# pico_tracker_v3_2.net
KiCad netlist of a schematic drawn in EAGLE
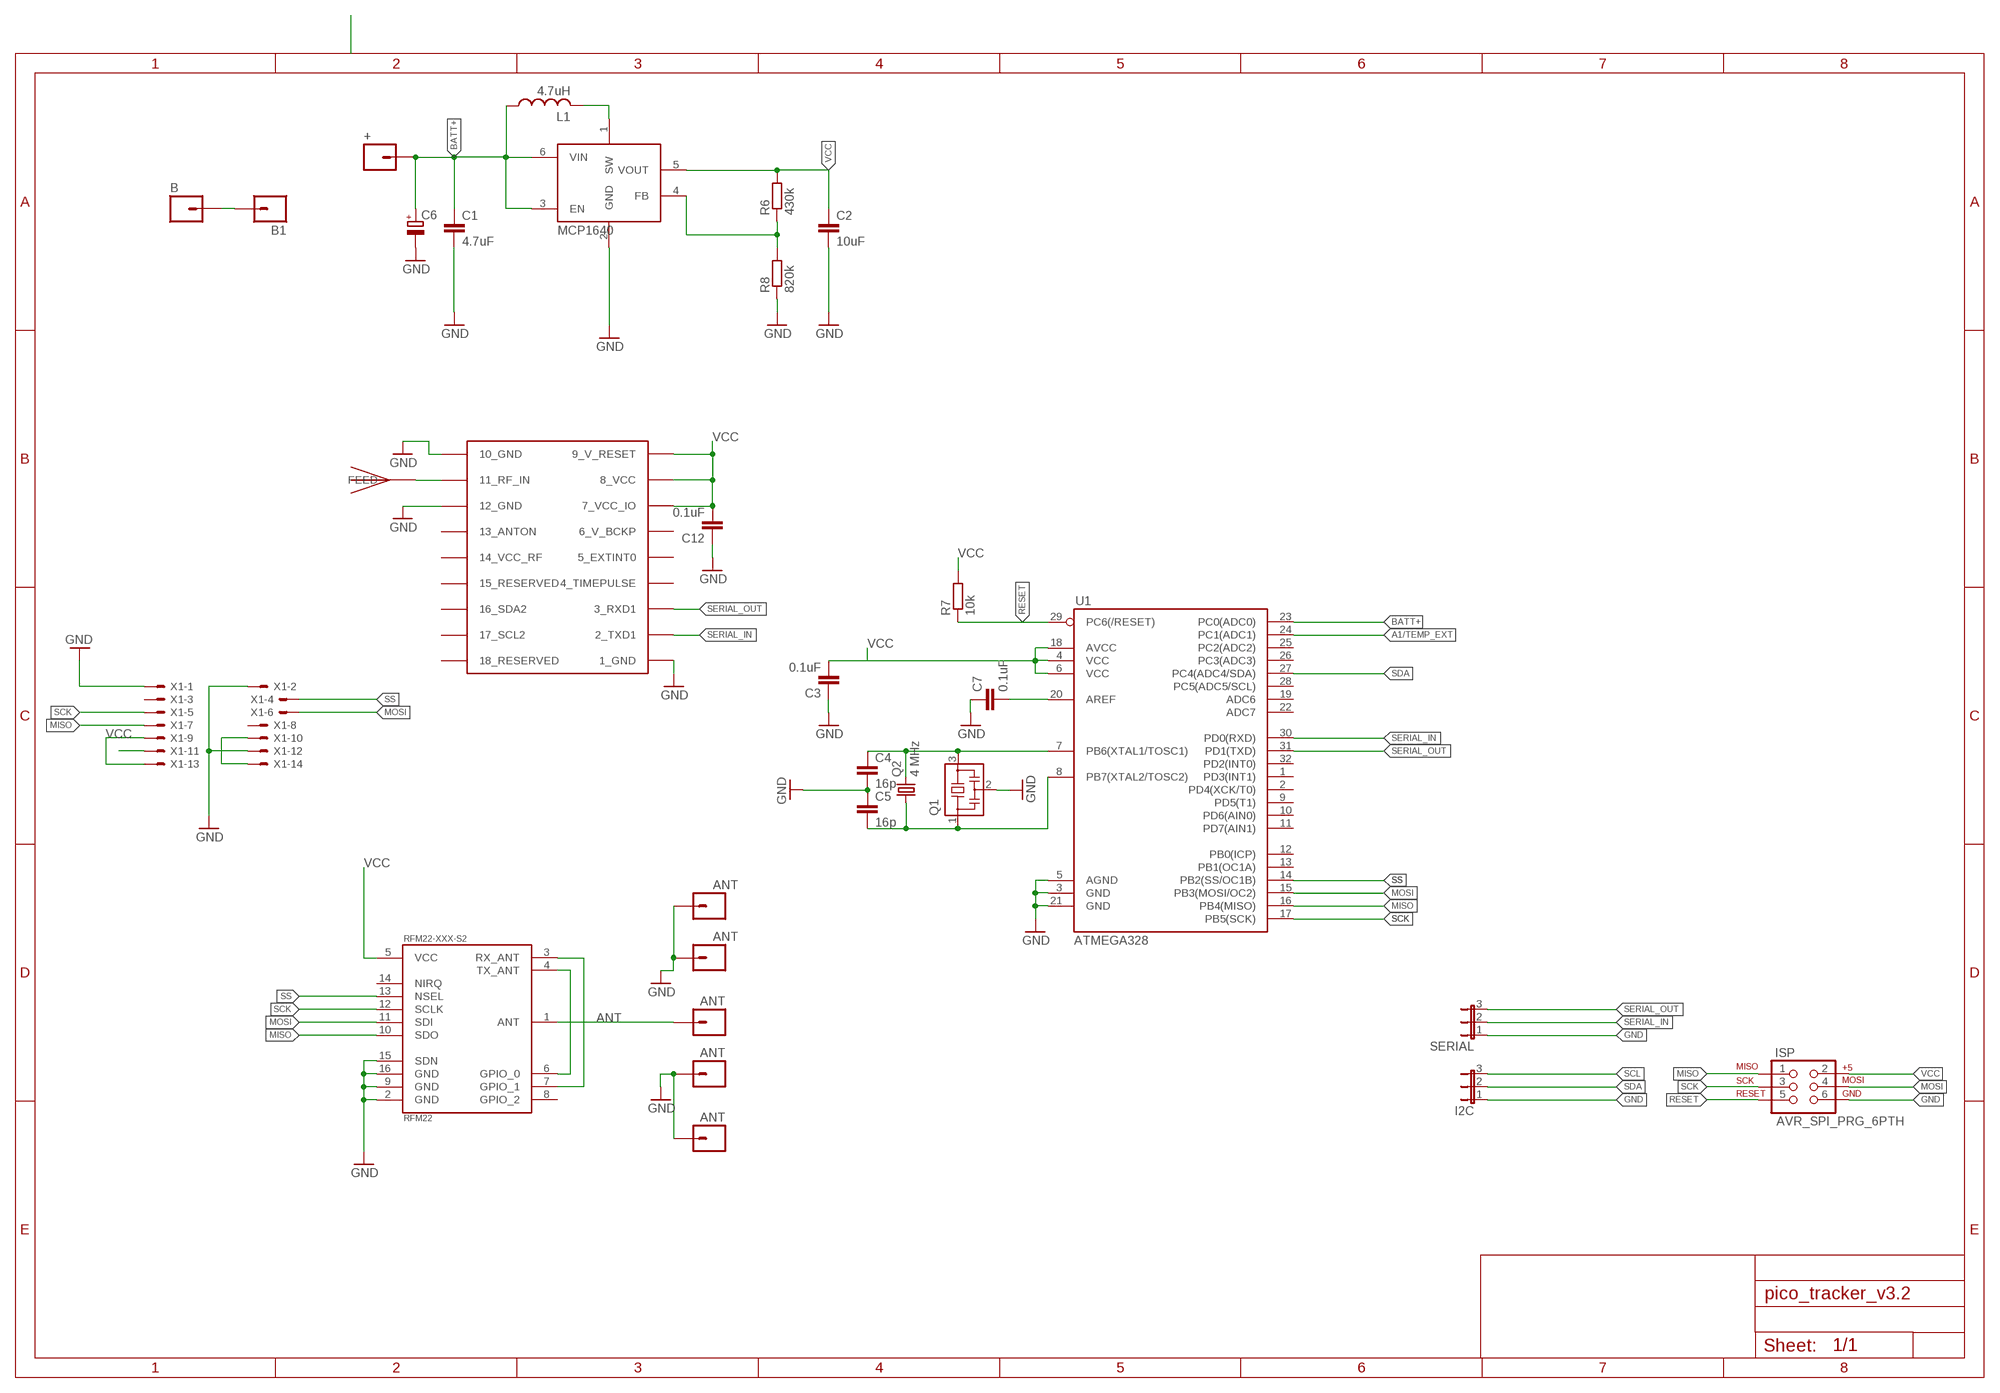
[diagram p0: schematic, sheet 1]

(export (version "E")
  (design (tool "Eeschema 10.0.6"))
  (components
    (comp (ref "+")
      (value "M01PTH")
      (footprint "eagle-import:1X01")
      (libsource (lib "eagle-import") (part "M01PTH"))
    )
    (comp (ref "B")
      (value "M01PTH")
      (footprint "eagle-import:1X01")
      (libsource (lib "eagle-import") (part "M01PTH"))
    )
    (comp (ref "B1")
      (value "M01PTH")
      (footprint "eagle-import:1X01")
      (libsource (lib "eagle-import") (part "M01PTH"))
    )
    (comp (ref "C1")
      (value "4.7uF")
      (footprint "eagle-import:C0805")
      (libsource (lib "eagle-import") (part "C-EUC0805"))
    )
    (comp (ref "C2")
      (value "10uF")
      (footprint "eagle-import:C0805")
      (libsource (lib "eagle-import") (part "C-EUC0805"))
    )
    (comp (ref "C3")
      (value "0.1uF")
      (footprint "eagle-import:C0603")
      (libsource (lib "eagle-import") (part "C-EUC0603"))
    )
    (comp (ref "C4")
      (value "16p")
      (footprint "eagle-import:C0603")
      (libsource (lib "eagle-import") (part "C-EUC0603"))
    )
    (comp (ref "C5")
      (value "16p")
      (footprint "eagle-import:C0603")
      (libsource (lib "eagle-import") (part "C-EUC0603"))
    )
    (comp (ref "C6")
      (value "CPOL-EUSMCD")
      (footprint "eagle-import:SMC_D")
      (libsource (lib "eagle-import") (part "CPOL-EUSMCD"))
    )
    (comp (ref "C7")
      (value "0.1uF")
      (footprint "eagle-import:C0603")
      (libsource (lib "eagle-import") (part "C-EUC0603"))
    )
    (comp (ref "C12")
      (value "0.1uF")
      (footprint "eagle-import:C0603")
      (libsource (lib "eagle-import") (part "C-EUC0603"))
    )
    (comp (ref "GND")
      (value "ANT")
      (footprint "eagle-import:1X01")
      (libsource (lib "eagle-import") (part "SparkFun_M01PTH"))
    )
    (comp (ref "GND17")
      (value "ANT")
      (footprint "eagle-import:1X01")
      (libsource (lib "eagle-import") (part "SparkFun_M01PTH"))
    )
    (comp (ref "GPS_ANT")
      (value "JTI_ANTENNA-1575AT43A40")
      (footprint "eagle-import:JTI_ANTENNA-1575AT43A40")
      (libsource (lib "eagle-import") (part "JTI_ANTENNA-1575AT43A40"))
    )
    (comp (ref "I2C")
      (value "JP2E")
      (footprint "eagle-import:JP2")
      (libsource (lib "eagle-import") (part "JP2E"))
    )
    (comp (ref "ISP")
      (value "AVR_SPI_PRG_6PTH")
      (footprint "eagle-import:2X3")
      (libsource (lib "eagle-import") (part "AVR_SPI_PRG_6PTH"))
    )
    (comp (ref "JP2")
      (value "ANT")
      (footprint "eagle-import:1X01")
      (libsource (lib "eagle-import") (part "SparkFun_M01PTH"))
    )
    (comp (ref "JP3")
      (value "ANT")
      (footprint "eagle-import:1X01")
      (libsource (lib "eagle-import") (part "SparkFun_M01PTH"))
    )
    (comp (ref "JP4")
      (value "ANT")
      (footprint "eagle-import:1X01")
      (libsource (lib "eagle-import") (part "SparkFun_M01PTH"))
    )
    (comp (ref "L1")
      (value "4.7uH")
      (footprint "eagle-import:LQH44")
      (libsource (lib "eagle-import") (part "LLQH44P_P0"))
    )
    (comp (ref "Q1")
      (value "CSTCR6M00G53Z")
      (footprint "eagle-import:CSTCR6M")
      (fields (field (name "MPN") "CSTCR6M00G53-R0"))
      (libsource (lib "eagle-import") (part "CSTCR6M00G53Z"))
    )
    (comp (ref "Q2")
      (value "4 MHz")
      (footprint "eagle-import:ABM03_HC49")
      (libsource (lib "eagle-import") (part "ABRACON_ABM3_CRYSTALABM03_HC49"))
    )
    (comp (ref "R6")
      (value "430k")
      (footprint "eagle-import:R0603")
      (libsource (lib "eagle-import") (part "R-EU_R0603"))
    )
    (comp (ref "R7")
      (value "10k")
      (footprint "eagle-import:R0603")
      (libsource (lib "eagle-import") (part "R-EU_R0603"))
    )
    (comp (ref "R8")
      (value "820k")
      (footprint "eagle-import:R0603")
      (libsource (lib "eagle-import") (part "R-EU_R0603"))
    )
    (comp (ref "RFM22-XXX-S2")
      (value "RFM22")
      (footprint "eagle-import:RFM22-XXX-S2")
      (libsource (lib "eagle-import") (part "RFM22"))
    )
    (comp (ref "SERIAL")
      (value "JP2E")
      (footprint "eagle-import:JP2")
      (libsource (lib "eagle-import") (part "JP2E"))
    )
    (comp (ref "U$3")
      (value "UBLOX_MAX-6")
      (footprint "eagle-import:UBLOX_MAX-6")
      (libsource (lib "eagle-import") (part "UBLOX_MAX-6"))
    )
    (comp (ref "U1")
      (value "ATMEGA328")
      (footprint "eagle-import:TQFP32-08")
      (libsource (lib "eagle-import") (part "ATMEGA168"))
    )
    (comp (ref "U2")
      (value "MCP1640")
      (footprint "eagle-import:SOT23-6")
      (libsource (lib "eagle-import") (part "MCP1640"))
    )
    (comp (ref "X1")
      (value "87758-1416")
      (footprint "eagle-import:87758-1416")
      (libsource (lib "eagle-import") (part "87758-1416"))
    )
  )
  (nets
    (net (code "1") (name "/ANT") (class "Default")
      (node (ref "JP2") (pin "1") (pinfunction "1_1") (pintype "passive"))
      (node (ref "RFM22-XXX-S2") (pin "1") (pinfunction "ANT_1") (pintype "bidirectional"))
    )
    (net (code "2") (name "A1{slash}TEMP_EXT") (class "Default")
      (node (ref "U1") (pin "24") (pinfunction "PC1(ADC1)_24") (pintype "bidirectional"))
    )
    (net (code "3") (name "BATT+") (class "Default")
      (node (ref "+") (pin "1") (pinfunction "1_1") (pintype "passive"))
      (node (ref "C1") (pin "1") (pinfunction "1_1") (pintype "passive"))
      (node (ref "C6") (pin "+") (pinfunction "+_+") (pintype "passive"))
      (node (ref "L1") (pin "P$1") (pinfunction "1_P$1") (pintype "passive"))
      (node (ref "U1") (pin "23") (pinfunction "PC0(ADC0)_23") (pintype "bidirectional"))
      (node (ref "U2") (pin "3") (pinfunction "EN_3") (pintype "input"))
      (node (ref "U2") (pin "6") (pinfunction "VIN_6") (pintype "input"))
    )
    (net (code "4") (name "GND") (class "Default")
      (node (ref "C1") (pin "2") (pinfunction "2_2") (pintype "passive"))
      (node (ref "C12") (pin "1") (pinfunction "1_1") (pintype "passive"))
      (node (ref "C2") (pin "2") (pinfunction "2_2") (pintype "passive"))
      (node (ref "C3") (pin "1") (pinfunction "1_1") (pintype "passive"))
      (node (ref "C4") (pin "2") (pinfunction "2_2") (pintype "passive"))
      (node (ref "C5") (pin "1") (pinfunction "1_1") (pintype "passive"))
      (node (ref "C6") (pin "-") (pinfunction "-_-") (pintype "passive"))
      (node (ref "C7") (pin "1") (pinfunction "1_1") (pintype "passive"))
      (node (ref "GND") (pin "1") (pinfunction "1_1") (pintype "passive"))
      (node (ref "GND17") (pin "1") (pinfunction "1_1") (pintype "passive"))
      (node (ref "I2C") (pin "1") (pinfunction "1_1") (pintype "passive"))
      (node (ref "ISP") (pin "6") (pinfunction "6_6") (pintype "passive"))
      (node (ref "JP3") (pin "1") (pinfunction "1_1") (pintype "passive"))
      (node (ref "JP4") (pin "1") (pinfunction "1_1") (pintype "passive"))
      (node (ref "Q1") (pin "2") (pinfunction "2_2") (pintype "passive"))
      (node (ref "R8") (pin "1") (pinfunction "1_1") (pintype "passive"))
      (node (ref "RFM22-XXX-S2") (pin "15") (pinfunction "SDN_15") (pintype "input"))
      (node (ref "RFM22-XXX-S2") (pin "16") (pinfunction "GND_16") (pintype "power_in"))
      (node (ref "RFM22-XXX-S2") (pin "2") (pinfunction "GND_2") (pintype "power_in"))
      (node (ref "RFM22-XXX-S2") (pin "9") (pinfunction "GND_9") (pintype "power_in"))
      (node (ref "SERIAL") (pin "1") (pinfunction "1_1") (pintype "passive"))
      (node (ref "U$3") (pin "10_GND") (pinfunction "10_GND_10_GND") (pintype "power_in"))
      (node (ref "U$3") (pin "12_GND") (pinfunction "12_GND_12_GND") (pintype "power_in"))
      (node (ref "U$3") (pin "1_GND") (pinfunction "1_GND_1_GND") (pintype "power_in"))
      (node (ref "U1") (pin "21") (pinfunction "GND_21") (pintype "bidirectional"))
      (node (ref "U1") (pin "3") (pinfunction "GND_3") (pintype "bidirectional"))
      (node (ref "U1") (pin "5") (pinfunction "AGND_5") (pintype "bidirectional"))
      (node (ref "U2") (pin "2") (pinfunction "GND_2") (pintype "power_in"))
      (node (ref "X1") (pin "1") (pinfunction "S_1") (pintype "passive"))
      (node (ref "X1") (pin "12") (pinfunction "S_12") (pintype "passive"))
      (node (ref "X1") (pin "2") (pinfunction "S_2") (pintype "passive"))
    )
    (net (code "5") (name "MISO") (class "Default")
      (node (ref "ISP") (pin "1") (pinfunction "1_1") (pintype "passive"))
      (node (ref "RFM22-XXX-S2") (pin "10") (pinfunction "SDO_10") (pintype "output"))
      (node (ref "U1") (pin "16") (pinfunction "PB4(MISO)_16") (pintype "bidirectional"))
      (node (ref "X1") (pin "7") (pinfunction "S_7") (pintype "passive"))
    )
    (net (code "6") (name "MOSI") (class "Default")
      (node (ref "ISP") (pin "4") (pinfunction "4_4") (pintype "passive"))
      (node (ref "RFM22-XXX-S2") (pin "11") (pinfunction "SDI_11") (pintype "input"))
      (node (ref "U1") (pin "15") (pinfunction "PB3(MOSI/OC2)_15") (pintype "bidirectional"))
      (node (ref "X1") (pin "6") (pinfunction "S_6") (pintype "passive"))
    )
    (net (code "7") (name "Net-(B-Pad1)") (class "Default")
      (node (ref "B") (pin "1") (pinfunction "1_1") (pintype "passive"))
      (node (ref "B1") (pin "1") (pinfunction "1_1") (pintype "passive"))
    )
    (net (code "8") (name "Net-(GPS_ANT-PadFEED)") (class "Default")
      (node (ref "GPS_ANT") (pin "FEED") (pinfunction "FEED_FEED") (pintype "bidirectional"))
      (node (ref "U$3") (pin "11_RF_IN") (pinfunction "11_RF_IN_11_RF_IN") (pintype "bidirectional"))
    )
    (net (code "9") (name "Net-(L1-2)") (class "Default")
      (node (ref "L1") (pin "P$2") (pinfunction "2_P$2") (pintype "passive"))
      (node (ref "U2") (pin "1") (pinfunction "SW_1") (pintype "output"))
    )
    (net (code "10") (name "Net-(RFM22-XXX-S2-GPIO_0)") (class "Default")
      (node (ref "RFM22-XXX-S2") (pin "4") (pinfunction "TX_ANT_4") (pintype "input"))
      (node (ref "RFM22-XXX-S2") (pin "6") (pinfunction "GPIO_0_6") (pintype "bidirectional"))
    )
    (net (code "11") (name "Net-(RFM22-XXX-S2-GPIO_1)") (class "Default")
      (node (ref "RFM22-XXX-S2") (pin "3") (pinfunction "RX_ANT_3") (pintype "input"))
      (node (ref "RFM22-XXX-S2") (pin "7") (pinfunction "GPIO_1_7") (pintype "bidirectional"))
    )
    (net (code "12") (name "Net-(U1-AREF)") (class "Default")
      (node (ref "C7") (pin "2") (pinfunction "2_2") (pintype "passive"))
      (node (ref "U1") (pin "20") (pinfunction "AREF_20") (pintype "bidirectional"))
    )
    (net (code "13") (name "Net-(U1-PB6(XTAL1{slash}TOSC1))") (class "Default")
      (node (ref "C4") (pin "1") (pinfunction "1_1") (pintype "passive"))
      (node (ref "Q1") (pin "3") (pinfunction "3_3") (pintype "passive"))
      (node (ref "Q2") (pin "2") (pinfunction "2_2") (pintype "passive"))
      (node (ref "U1") (pin "7") (pinfunction "PB6(XTAL1/TOSC1)_7") (pintype "bidirectional"))
    )
    (net (code "14") (name "Net-(U1-PB7(XTAL2{slash}TOSC2))") (class "Default")
      (node (ref "C5") (pin "2") (pinfunction "2_2") (pintype "passive"))
      (node (ref "Q1") (pin "1") (pinfunction "1_1") (pintype "passive"))
      (node (ref "Q2") (pin "1") (pinfunction "1_1") (pintype "passive"))
      (node (ref "U1") (pin "8") (pinfunction "PB7(XTAL2/TOSC2)_8") (pintype "bidirectional"))
    )
    (net (code "15") (name "Net-(U2-FB)") (class "Default")
      (node (ref "R6") (pin "1") (pinfunction "1_1") (pintype "passive"))
      (node (ref "R8") (pin "2") (pinfunction "2_2") (pintype "passive"))
      (node (ref "U2") (pin "4") (pinfunction "FB_4") (pintype "input"))
    )
    (net (code "16") (name "Net-(X1B-S)") (class "Default")
      (node (ref "X1") (pin "10") (pinfunction "S_10") (pintype "passive"))
      (node (ref "X1") (pin "14") (pinfunction "S_14") (pintype "passive"))
    )
    (net (code "17") (name "Net-(X1E-S)") (class "Default")
      (node (ref "X1") (pin "13") (pinfunction "S_13") (pintype "passive"))
      (node (ref "X1") (pin "9") (pinfunction "S_9") (pintype "passive"))
    )
    (net (code "18") (name "RESET") (class "Default")
      (node (ref "ISP") (pin "5") (pinfunction "5_5") (pintype "passive"))
      (node (ref "R7") (pin "1") (pinfunction "1_1") (pintype "passive"))
      (node (ref "U1") (pin "29") (pinfunction "PC6(/RESET)_29") (pintype "bidirectional"))
    )
    (net (code "19") (name "SCK") (class "Default")
      (node (ref "ISP") (pin "3") (pinfunction "3_3") (pintype "passive"))
      (node (ref "RFM22-XXX-S2") (pin "12") (pinfunction "SCLK_12") (pintype "input"))
      (node (ref "U1") (pin "17") (pinfunction "PB5(SCK)_17") (pintype "bidirectional"))
      (node (ref "X1") (pin "5") (pinfunction "S_5") (pintype "passive"))
    )
    (net (code "20") (name "SCL") (class "Default")
      (node (ref "I2C") (pin "3") (pinfunction "3_3") (pintype "passive"))
    )
    (net (code "21") (name "SDA") (class "Default")
      (node (ref "I2C") (pin "2") (pinfunction "2_2") (pintype "passive"))
      (node (ref "U1") (pin "27") (pinfunction "PC4(ADC4/SDA)_27") (pintype "bidirectional"))
    )
    (net (code "22") (name "SERIAL_IN") (class "Default")
      (node (ref "SERIAL") (pin "2") (pinfunction "2_2") (pintype "passive"))
      (node (ref "U$3") (pin "2_TXD1") (pinfunction "2_TXD1_2_TXD1") (pintype "bidirectional"))
      (node (ref "U1") (pin "30") (pinfunction "PD0(RXD)_30") (pintype "bidirectional"))
    )
    (net (code "23") (name "SERIAL_OUT") (class "Default")
      (node (ref "SERIAL") (pin "3") (pinfunction "3_3") (pintype "passive"))
      (node (ref "U$3") (pin "3_RXD1") (pinfunction "3_RXD1_3_RXD1") (pintype "bidirectional"))
      (node (ref "U1") (pin "31") (pinfunction "PD1(TXD)_31") (pintype "bidirectional"))
    )
    (net (code "24") (name "SS") (class "Default")
      (node (ref "RFM22-XXX-S2") (pin "13") (pinfunction "NSEL_13") (pintype "input"))
      (node (ref "U1") (pin "14") (pinfunction "PB2(SS/OC1B)_14") (pintype "bidirectional"))
      (node (ref "X1") (pin "4") (pinfunction "S_4") (pintype "passive"))
    )
    (net (code "25") (name "VCC") (class "Default")
      (node (ref "C12") (pin "2") (pinfunction "2_2") (pintype "passive"))
      (node (ref "C2") (pin "1") (pinfunction "1_1") (pintype "passive"))
      (node (ref "C3") (pin "2") (pinfunction "2_2") (pintype "passive"))
      (node (ref "ISP") (pin "2") (pinfunction "2_2") (pintype "passive"))
      (node (ref "R6") (pin "2") (pinfunction "2_2") (pintype "passive"))
      (node (ref "R7") (pin "2") (pinfunction "2_2") (pintype "passive"))
      (node (ref "RFM22-XXX-S2") (pin "5") (pinfunction "VCC_5") (pintype "bidirectional"))
      (node (ref "U$3") (pin "7_VCC_IO") (pinfunction "7_VCC_IO_7_VCC_IO") (pintype "power_in"))
      (node (ref "U$3") (pin "8_VCC") (pinfunction "8_VCC_8_VCC") (pintype "power_in"))
      (node (ref "U$3") (pin "9_V_RESET") (pinfunction "9_V_RESET_9_V_RESET") (pintype "power_in"))
      (node (ref "U1") (pin "18") (pinfunction "AVCC_18") (pintype "bidirectional"))
      (node (ref "U1") (pin "4") (pinfunction "VCC_4") (pintype "bidirectional"))
      (node (ref "U1") (pin "6") (pinfunction "VCC_6") (pintype "bidirectional"))
      (node (ref "U2") (pin "5") (pinfunction "VOUT_5") (pintype "output"))
      (node (ref "X1") (pin "11") (pinfunction "S_11") (pintype "passive"))
    )
    (net (code "26") (name "unconnected-(RFM22-XXX-S2-GPIO_2-Pad8)") (class "Default")
      (node (ref "RFM22-XXX-S2") (pin "8") (pinfunction "GPIO_2_8") (pintype "bidirectional"))
    )
    (net (code "27") (name "unconnected-(RFM22-XXX-S2-NIRQ-Pad14)") (class "Default")
      (node (ref "RFM22-XXX-S2") (pin "14") (pinfunction "NIRQ_14") (pintype "output"))
    )
    (net (code "28") (name "unconnected-(U$3-Pad4_TIMEPULSE)") (class "Default")
      (node (ref "U$3") (pin "4_TIMEPULSE") (pinfunction "4_TIMEPULSE_4_TIMEPULSE") (pintype "bidirectional"))
    )
    (net (code "29") (name "unconnected-(U$3-Pad5_EXTINT0)") (class "Default")
      (node (ref "U$3") (pin "5_EXTINT0") (pinfunction "5_EXTINT0_5_EXTINT0") (pintype "bidirectional"))
    )
    (net (code "30") (name "unconnected-(U$3-Pad6_V_BCKP)") (class "Default")
      (node (ref "U$3") (pin "6_V_BCKP") (pinfunction "6_V_BCKP_6_V_BCKP") (pintype "bidirectional"))
    )
    (net (code "31") (name "unconnected-(U$3-Pad13_ANTON)") (class "Default")
      (node (ref "U$3") (pin "13_ANTON") (pinfunction "13_ANTON_13_ANTON") (pintype "bidirectional"))
    )
    (net (code "32") (name "unconnected-(U$3-Pad14_VCC_RF)") (class "Default")
      (node (ref "U$3") (pin "14_VCC_RF") (pinfunction "14_VCC_RF_14_VCC_RF") (pintype "bidirectional"))
    )
    (net (code "33") (name "unconnected-(U$3-Pad15_RESERVED)") (class "Default")
      (node (ref "U$3") (pin "15_RESERVED") (pinfunction "15_RESERVED_15_RESERVED") (pintype "bidirectional"))
    )
    (net (code "34") (name "unconnected-(U$3-Pad16_SDA2)") (class "Default")
      (node (ref "U$3") (pin "16_SDA2") (pinfunction "16_SDA2_16_SDA2") (pintype "bidirectional"))
    )
    (net (code "35") (name "unconnected-(U$3-Pad17_SCL2)") (class "Default")
      (node (ref "U$3") (pin "17_SCL2") (pinfunction "17_SCL2_17_SCL2") (pintype "bidirectional"))
    )
    (net (code "36") (name "unconnected-(U$3-Pad18_RESERVED)") (class "Default")
      (node (ref "U$3") (pin "18_RESERVED") (pinfunction "18_RESERVED_18_RESERVED") (pintype "bidirectional"))
    )
    (net (code "37") (name "unconnected-(U1-ADC6-Pad19)") (class "Default")
      (node (ref "U1") (pin "19") (pinfunction "ADC6_19") (pintype "bidirectional"))
    )
    (net (code "38") (name "unconnected-(U1-ADC7-Pad22)") (class "Default")
      (node (ref "U1") (pin "22") (pinfunction "ADC7_22") (pintype "bidirectional"))
    )
    (net (code "39") (name "unconnected-(U1-PB0(ICP)-Pad12)") (class "Default")
      (node (ref "U1") (pin "12") (pinfunction "PB0(ICP)_12") (pintype "bidirectional"))
    )
    (net (code "40") (name "unconnected-(U1-PB1(OC1A)-Pad13)") (class "Default")
      (node (ref "U1") (pin "13") (pinfunction "PB1(OC1A)_13") (pintype "bidirectional"))
    )
    (net (code "41") (name "unconnected-(U1-PC2(ADC2)-Pad25)") (class "Default")
      (node (ref "U1") (pin "25") (pinfunction "PC2(ADC2)_25") (pintype "bidirectional"))
    )
    (net (code "42") (name "unconnected-(U1-PC3(ADC3)-Pad26)") (class "Default")
      (node (ref "U1") (pin "26") (pinfunction "PC3(ADC3)_26") (pintype "bidirectional"))
    )
    (net (code "43") (name "unconnected-(U1-PC5(ADC5{slash}SCL)-Pad28)") (class "Default")
      (node (ref "U1") (pin "28") (pinfunction "PC5(ADC5/SCL)_28") (pintype "bidirectional"))
    )
    (net (code "44") (name "unconnected-(U1-PD2(INT0)-Pad32)") (class "Default")
      (node (ref "U1") (pin "32") (pinfunction "PD2(INT0)_32") (pintype "bidirectional"))
    )
    (net (code "45") (name "unconnected-(U1-PD3(INT1)-Pad1)") (class "Default")
      (node (ref "U1") (pin "1") (pinfunction "PD3(INT1)_1") (pintype "bidirectional"))
    )
    (net (code "46") (name "unconnected-(U1-PD4(XCK{slash}T0)-Pad2)") (class "Default")
      (node (ref "U1") (pin "2") (pinfunction "PD4(XCK/T0)_2") (pintype "bidirectional"))
    )
    (net (code "47") (name "unconnected-(U1-PD5(T1)-Pad9)") (class "Default")
      (node (ref "U1") (pin "9") (pinfunction "PD5(T1)_9") (pintype "bidirectional"))
    )
    (net (code "48") (name "unconnected-(U1-PD6(AIN0)-Pad10)") (class "Default")
      (node (ref "U1") (pin "10") (pinfunction "PD6(AIN0)_10") (pintype "bidirectional"))
    )
    (net (code "49") (name "unconnected-(U1-PD7(AIN1)-Pad11)") (class "Default")
      (node (ref "U1") (pin "11") (pinfunction "PD7(AIN1)_11") (pintype "bidirectional"))
    )
    (net (code "50") (name "unconnected-(X1H-S-Pad3)") (class "Default")
      (node (ref "X1") (pin "3") (pinfunction "S_3") (pintype "passive"))
    )
    (net (code "51") (name "unconnected-(X1M-S-Pad8)") (class "Default")
      (node (ref "X1") (pin "8") (pinfunction "S_8") (pintype "passive"))
    )
  )
)
